# 4fader_Sub.net
KiCad netlist of a schematic drawn in Altium Designer
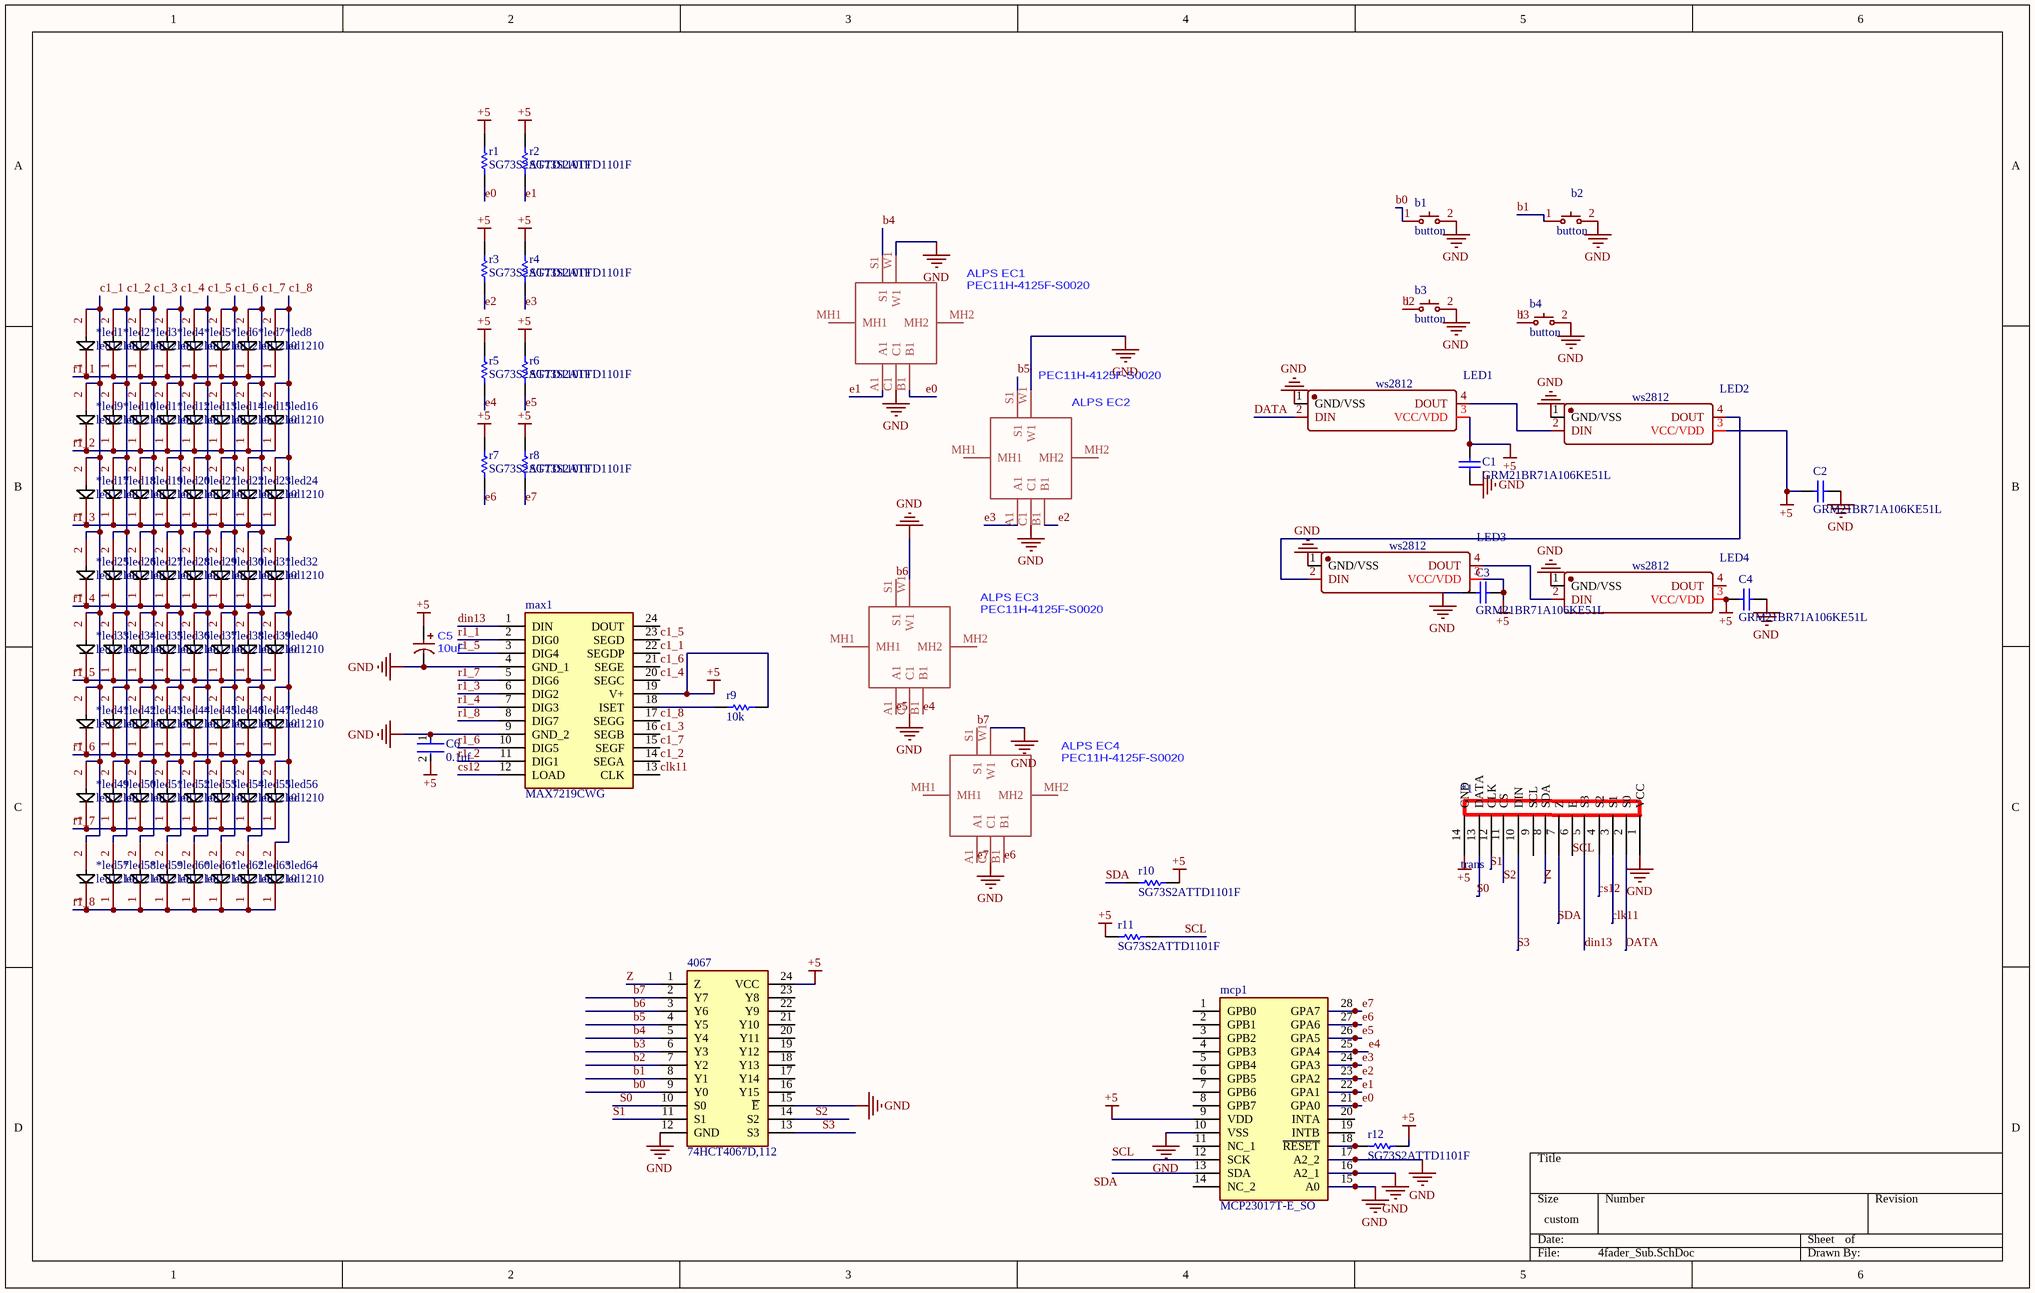
[diagram p0: 4fader_Sub.SchDoc]

(export (version "E")
  (design (tool "Eeschema 10.0.6"))
  (components
    (comp (ref "*1")
      (value "trans")
      (footprint "FPC-SMD_KH-FG1.0-H2.0-14PIN")
      (libsource (lib "sub_1") (part "trans"))
    )
    (comp (ref "*led1") (value "led1210") (footprint "1210贴片led") (libsource (lib "8") (part "led1210")))
    (comp (ref "*led2") (value "led1210") (footprint "1210贴片led") (libsource (lib "8") (part "led1210")))
    (comp (ref "*led3") (value "led1210") (footprint "1210贴片led") (libsource (lib "8") (part "led1210")))
    (comp (ref "*led4") (value "led1210") (footprint "1210贴片led") (libsource (lib "8") (part "led1210")))
    (comp (ref "*led5") (value "led1210") (footprint "1210贴片led") (libsource (lib "8") (part "led1210")))
    (comp (ref "*led6") (value "led1210") (footprint "1210贴片led") (libsource (lib "8") (part "led1210")))
    (comp (ref "*led7") (value "led1210") (footprint "1210贴片led") (libsource (lib "8") (part "led1210")))
    (comp (ref "*led8") (value "led1210") (footprint "1210贴片led") (libsource (lib "8") (part "led1210")))
    (comp (ref "*led9") (value "led1210") (footprint "1210贴片led") (libsource (lib "8") (part "led1210")))
    (comp (ref "*led10") (value "led1210") (footprint "1210贴片led") (libsource (lib "8") (part "led1210")))
    (comp (ref "*led11") (value "led1210") (footprint "1210贴片led") (libsource (lib "8") (part "led1210")))
    (comp (ref "*led12") (value "led1210") (footprint "1210贴片led") (libsource (lib "8") (part "led1210")))
    (comp (ref "*led13") (value "led1210") (footprint "1210贴片led") (libsource (lib "8") (part "led1210")))
    (comp (ref "*led14") (value "led1210") (footprint "1210贴片led") (libsource (lib "8") (part "led1210")))
    (comp (ref "*led15") (value "led1210") (footprint "1210贴片led") (libsource (lib "8") (part "led1210")))
    (comp (ref "*led16") (value "led1210") (footprint "1210贴片led") (libsource (lib "8") (part "led1210")))
    (comp (ref "*led17") (value "led1210") (footprint "1210贴片led") (libsource (lib "8") (part "led1210")))
    (comp (ref "*led18") (value "led1210") (footprint "1210贴片led") (libsource (lib "8") (part "led1210")))
    (comp (ref "*led19") (value "led1210") (footprint "1210贴片led") (libsource (lib "8") (part "led1210")))
    (comp (ref "*led20") (value "led1210") (footprint "1210贴片led") (libsource (lib "8") (part "led1210")))
    (comp (ref "*led21") (value "led1210") (footprint "1210贴片led") (libsource (lib "8") (part "led1210")))
    (comp (ref "*led22") (value "led1210") (footprint "1210贴片led") (libsource (lib "8") (part "led1210")))
    (comp (ref "*led23") (value "led1210") (footprint "1210贴片led") (libsource (lib "8") (part "led1210")))
    (comp (ref "*led24") (value "led1210") (footprint "1210贴片led") (libsource (lib "8") (part "led1210")))
    (comp (ref "*led25") (value "led1210") (footprint "1210贴片led") (libsource (lib "8") (part "led1210")))
    (comp (ref "*led26") (value "led1210") (footprint "1210贴片led") (libsource (lib "8") (part "led1210")))
    (comp (ref "*led27") (value "led1210") (footprint "1210贴片led") (libsource (lib "8") (part "led1210")))
    (comp (ref "*led28") (value "led1210") (footprint "1210贴片led") (libsource (lib "8") (part "led1210")))
    (comp (ref "*led29") (value "led1210") (footprint "1210贴片led") (libsource (lib "8") (part "led1210")))
    (comp (ref "*led30") (value "led1210") (footprint "1210贴片led") (libsource (lib "8") (part "led1210")))
    (comp (ref "*led31") (value "led1210") (footprint "1210贴片led") (libsource (lib "8") (part "led1210")))
    (comp (ref "*led32") (value "led1210") (footprint "1210贴片led") (libsource (lib "8") (part "led1210")))
    (comp (ref "*led33") (value "led1210") (footprint "1210贴片led") (libsource (lib "8") (part "led1210")))
    (comp (ref "*led34") (value "led1210") (footprint "1210贴片led") (libsource (lib "8") (part "led1210")))
    (comp (ref "*led35") (value "led1210") (footprint "1210贴片led") (libsource (lib "8") (part "led1210")))
    (comp (ref "*led36") (value "led1210") (footprint "1210贴片led") (libsource (lib "8") (part "led1210")))
    (comp (ref "*led37") (value "led1210") (footprint "1210贴片led") (libsource (lib "8") (part "led1210")))
    (comp (ref "*led38") (value "led1210") (footprint "1210贴片led") (libsource (lib "8") (part "led1210")))
    (comp (ref "*led39") (value "led1210") (footprint "1210贴片led") (libsource (lib "8") (part "led1210")))
    (comp (ref "*led40") (value "led1210") (footprint "1210贴片led") (libsource (lib "8") (part "led1210")))
    (comp (ref "*led41") (value "led1210") (footprint "1210贴片led") (libsource (lib "8") (part "led1210")))
    (comp (ref "*led42") (value "led1210") (footprint "1210贴片led") (libsource (lib "8") (part "led1210")))
    (comp (ref "*led43") (value "led1210") (footprint "1210贴片led") (libsource (lib "8") (part "led1210")))
    (comp (ref "*led44") (value "led1210") (footprint "1210贴片led") (libsource (lib "8") (part "led1210")))
    (comp (ref "*led45") (value "led1210") (footprint "1210贴片led") (libsource (lib "8") (part "led1210")))
    (comp (ref "*led46") (value "led1210") (footprint "1210贴片led") (libsource (lib "8") (part "led1210")))
    (comp (ref "*led47") (value "led1210") (footprint "1210贴片led") (libsource (lib "8") (part "led1210")))
    (comp (ref "*led48") (value "led1210") (footprint "1210贴片led") (libsource (lib "8") (part "led1210")))
    (comp (ref "*led49") (value "led1210") (footprint "1210贴片led") (libsource (lib "8") (part "led1210")))
    (comp (ref "*led50") (value "led1210") (footprint "1210贴片led") (libsource (lib "8") (part "led1210")))
    (comp (ref "*led51") (value "led1210") (footprint "1210贴片led") (libsource (lib "8") (part "led1210")))
    (comp (ref "*led52") (value "led1210") (footprint "1210贴片led") (libsource (lib "8") (part "led1210")))
    (comp (ref "*led53") (value "led1210") (footprint "1210贴片led") (libsource (lib "8") (part "led1210")))
    (comp (ref "*led54") (value "led1210") (footprint "1210贴片led") (libsource (lib "8") (part "led1210")))
    (comp (ref "*led55") (value "led1210") (footprint "1210贴片led") (libsource (lib "8") (part "led1210")))
    (comp (ref "*led56") (value "led1210") (footprint "1210贴片led") (libsource (lib "8") (part "led1210")))
    (comp (ref "*led57") (value "led1210") (footprint "1210贴片led") (libsource (lib "8") (part "led1210")))
    (comp (ref "*led58") (value "led1210") (footprint "1210贴片led") (libsource (lib "8") (part "led1210")))
    (comp (ref "*led59") (value "led1210") (footprint "1210贴片led") (libsource (lib "8") (part "led1210")))
    (comp (ref "*led60") (value "led1210") (footprint "1210贴片led") (libsource (lib "8") (part "led1210")))
    (comp (ref "*led61") (value "led1210") (footprint "1210贴片led") (libsource (lib "8") (part "led1210")))
    (comp (ref "*led62") (value "led1210") (footprint "1210贴片led") (libsource (lib "8") (part "led1210")))
    (comp (ref "*led63") (value "led1210") (footprint "1210贴片led") (libsource (lib "8") (part "led1210")))
    (comp (ref "*led64") (value "led1210") (footprint "1210贴片led") (libsource (lib "8") (part "led1210")))
    (comp (ref "4067")
      (value "74HCT4067D,112")
      (footprint "SamacSys:SOIC127P1032X265-24N")
      (description "Integrated Circuit")
      (fields (field (name "MOUSER PART NUMBER") "771-74HCT4067D"))
      (libsource (lib "*") (part "74HCT4067D,112"))
    )
    (comp (ref "ALPS EC1")
      (value "PEC11H-4125F-S0020")
      (footprint "ALPS EC11")
      (libsource (lib "8") (part "PEC11H-4125F-S0020"))
    )
    (comp (ref "ALPS EC2")
      (value "PEC11H-4125F-S0020")
      (footprint "ALPS EC11")
      (libsource (lib "8") (part "PEC11H-4125F-S0020"))
    )
    (comp (ref "ALPS EC3")
      (value "PEC11H-4125F-S0020")
      (footprint "ALPS EC11")
      (libsource (lib "8") (part "PEC11H-4125F-S0020"))
    )
    (comp (ref "ALPS EC4")
      (value "PEC11H-4125F-S0020")
      (footprint "ALPS EC11")
      (libsource (lib "8") (part "PEC11H-4125F-S0020"))
    )
    (comp (ref "b1") (value "button") (footprint "BUTTON") (libsource (lib "8") (part "button")))
    (comp (ref "b2") (value "button") (footprint "BUTTON") (libsource (lib "8") (part "button")))
    (comp (ref "b3") (value "button") (footprint "BUTTON") (libsource (lib "8") (part "button")))
    (comp (ref "b4") (value "button") (footprint "BUTTON") (libsource (lib "8") (part "button")))
    (comp (ref "C1")
      (value "GRM21BR71A106KE51L")
      (footprint "CAPC2013X140X45LL15T25")
      (fields (field (name "MANUFACTURER") "Murata"))
      (libsource (lib "sub_1") (part "CMP-2007-03395-1"))
    )
    (comp (ref "C2")
      (value "GRM21BR71A106KE51L")
      (footprint "CAPC2013X140X45LL15T25")
      (fields (field (name "MANUFACTURER") "Murata"))
      (libsource (lib "sub_1") (part "CMP-2007-03395-1"))
    )
    (comp (ref "C3")
      (value "GRM21BR71A106KE51L")
      (footprint "CAPC2013X140X45LL15T25")
      (fields (field (name "MANUFACTURER") "Murata"))
      (libsource (lib "sub_1") (part "CMP-2007-03395-1"))
    )
    (comp (ref "C4")
      (value "GRM21BR71A106KE51L")
      (footprint "CAPC2013X140X45LL15T25")
      (fields (field (name "MANUFACTURER") "Murata"))
      (libsource (lib "sub_1") (part "CMP-2007-03395-1"))
    )
    (comp (ref "C5")
      (value "10uF")
      (footprint "ELECTROLYTIC CAPACITOR SMD 4X5.4")
      (libsource (lib "sub_1") (part "4.3 X 4.3 ELECTROLYTIC  CAPACITOR SMD μF"))
    )
    (comp (ref "C6")
      (value "0.1uf")
      (footprint "FP-CC0805-0_85-IPC_A")
      (description "CAP CER 0.1UF 25V X7R 0805")
      (fields (field (name "MANUFACTURER PART NUMBER") "CC0805KRX7R8BB104") (field (name "TOLERANCE") "0.1"))
      (libsource (lib "sub_1") (part "CMP-1036-04410-2"))
    )
    (comp (ref "LED1") (value "ws2812") (footprint "ws2812") (libsource (lib "8") (part "ws2812")))
    (comp (ref "LED2") (value "ws2812") (footprint "ws2812") (libsource (lib "8") (part "ws2812")))
    (comp (ref "LED3") (value "ws2812") (footprint "ws2812") (libsource (lib "8") (part "ws2812")))
    (comp (ref "LED4") (value "ws2812") (footprint "ws2812") (libsource (lib "8") (part "ws2812")))
    (comp (ref "max1")
      (value "MAX7219CWG")
      (footprint "SamacSys:SOIC127P1032X265-24N")
      (description "Integrated Circuit")
      (fields (field (name "MOUSER PART NUMBER") "700-MAX7219CWG-NR"))
      (libsource (lib "*") (part "MAX7219CWG"))
    )
    (comp (ref "mcp1")
      (value "MCP23017T-E_SO")
      (footprint "SOIC127P1030X265-28N")
      (description "Integrated Circuit")
      (fields
        (field (name "MANUFACTURER_PART_NUMBER") "MCP23017T-E/SO")
        (field (name "MOUSER PART NUMBER") "579-MCP23017T-E/SO")
      )
      (libsource (lib "sub_1") (part "MCP23017T-E_SO"))
    )
    (comp (ref "r1")
      (value "SG73S2ATTD1101F")
      (footprint "RESC2013X60X30LL20T20")
      (fields (field (name "MANUFACTURER") "KOA Speer"))
      (libsource (lib "sub_1") (part "CMP-2001-02660-1"))
    )
    (comp (ref "r2")
      (value "SG73S2ATTD1101F")
      (footprint "RESC2013X60X30LL20T20")
      (fields (field (name "MANUFACTURER") "KOA Speer"))
      (libsource (lib "sub_1") (part "CMP-2001-02660-1"))
    )
    (comp (ref "r3")
      (value "SG73S2ATTD1101F")
      (footprint "RESC2013X60X30LL20T20")
      (fields (field (name "MANUFACTURER") "KOA Speer"))
      (libsource (lib "sub_1") (part "CMP-2001-02660-1"))
    )
    (comp (ref "r4")
      (value "SG73S2ATTD1101F")
      (footprint "RESC2013X60X30LL20T20")
      (fields (field (name "MANUFACTURER") "KOA Speer"))
      (libsource (lib "sub_1") (part "CMP-2001-02660-1"))
    )
    (comp (ref "r5")
      (value "SG73S2ATTD1101F")
      (footprint "RESC2013X60X30LL20T20")
      (fields (field (name "MANUFACTURER") "KOA Speer"))
      (libsource (lib "sub_1") (part "CMP-2001-02660-1"))
    )
    (comp (ref "r6")
      (value "SG73S2ATTD1101F")
      (footprint "RESC2013X60X30LL20T20")
      (fields (field (name "MANUFACTURER") "KOA Speer"))
      (libsource (lib "sub_1") (part "CMP-2001-02660-1"))
    )
    (comp (ref "r7")
      (value "SG73S2ATTD1101F")
      (footprint "RESC2013X60X30LL20T20")
      (fields (field (name "MANUFACTURER") "KOA Speer"))
      (libsource (lib "sub_1") (part "CMP-2001-02660-1"))
    )
    (comp (ref "r8")
      (value "SG73S2ATTD1101F")
      (footprint "RESC2013X60X30LL20T20")
      (fields (field (name "MANUFACTURER") "KOA Speer"))
      (libsource (lib "sub_1") (part "CMP-2001-02660-1"))
    )
    (comp (ref "r9")
      (value "10k")
      (footprint "RESC2013X60X30LL20T20")
      (fields (field (name "MANUFACTURER") "KOA Speer") (field (name "PART NUMBER") "SG73S2ATTD1101F"))
      (libsource (lib "sub_1") (part "CMP-2001-02660-1"))
    )
    (comp (ref "r10")
      (value "SG73S2ATTD1101F")
      (footprint "RESC2013X60X30LL20T20")
      (fields (field (name "MANUFACTURER") "KOA Speer"))
      (libsource (lib "sub_1") (part "CMP-2001-02660-1"))
    )
    (comp (ref "r11")
      (value "SG73S2ATTD1101F")
      (footprint "RESC2013X60X30LL20T20")
      (fields (field (name "MANUFACTURER") "KOA Speer"))
      (libsource (lib "sub_1") (part "CMP-2001-02660-1"))
    )
    (comp (ref "r12")
      (value "SG73S2ATTD1101F")
      (footprint "RESC2013X60X30LL20T20")
      (fields (field (name "MANUFACTURER") "KOA Speer"))
      (libsource (lib "sub_1") (part "CMP-2001-02660-1"))
    )
  )
  (nets
    (net (code "1") (name "+5") (class "Default")
      (node (ref "*1") (pin "14") (pinfunction "GND_14") (pintype "passive"))
      (node (ref "4067") (pin "24") (pinfunction "VCC_24") (pintype "passive"))
      (node (ref "C1") (pin "2") (pinfunction "2_2") (pintype "passive"))
      (node (ref "C2") (pin "1") (pinfunction "1_1") (pintype "passive"))
      (node (ref "C3") (pin "2") (pinfunction "2_2") (pintype "passive"))
      (node (ref "C4") (pin "1") (pinfunction "1_1") (pintype "passive"))
      (node (ref "C5") (pin "1") (pinfunction "1_1") (pintype "passive"))
      (node (ref "C6") (pin "2") (pinfunction "2_2") (pintype "passive"))
      (node (ref "LED1") (pin "3") (pinfunction "VCC/VDD_3") (pintype "passive"))
      (node (ref "LED2") (pin "3") (pinfunction "VCC/VDD_3") (pintype "passive"))
      (node (ref "LED3") (pin "3") (pinfunction "VCC/VDD_3") (pintype "passive"))
      (node (ref "LED4") (pin "3") (pinfunction "VCC/VDD_3") (pintype "passive"))
      (node (ref "max1") (pin "19") (pinfunction "V+_19") (pintype "passive"))
      (node (ref "mcp1") (pin "9") (pinfunction "VDD_9") (pintype "passive"))
      (node (ref "r1") (pin "2") (pinfunction "2_2") (pintype "passive"))
      (node (ref "r10") (pin "2") (pinfunction "2_2") (pintype "passive"))
      (node (ref "r11") (pin "2") (pinfunction "2_2") (pintype "passive"))
      (node (ref "r12") (pin "2") (pinfunction "2_2") (pintype "passive"))
      (node (ref "r2") (pin "2") (pinfunction "2_2") (pintype "passive"))
      (node (ref "r3") (pin "2") (pinfunction "2_2") (pintype "passive"))
      (node (ref "r4") (pin "2") (pinfunction "2_2") (pintype "passive"))
      (node (ref "r5") (pin "2") (pinfunction "2_2") (pintype "passive"))
      (node (ref "r6") (pin "2") (pinfunction "2_2") (pintype "passive"))
      (node (ref "r7") (pin "2") (pinfunction "2_2") (pintype "passive"))
      (node (ref "r8") (pin "2") (pinfunction "2_2") (pintype "passive"))
      (node (ref "r9") (pin "2") (pinfunction "2_2") (pintype "passive"))
    )
    (net (code "2") (name "/DATA") (class "Default")
      (node (ref "*1") (pin "2") (pinfunction "S0_2") (pintype "passive"))
      (node (ref "LED1") (pin "2") (pinfunction "DIN_2") (pintype "passive"))
    )
    (net (code "3") (name "/S0") (class "Default")
      (node (ref "*1") (pin "13") (pinfunction "DATA_13") (pintype "passive"))
      (node (ref "4067") (pin "10") (pinfunction "S0_10") (pintype "passive"))
    )
    (net (code "4") (name "/S1") (class "Default")
      (node (ref "*1") (pin "12") (pinfunction "CLK_12") (pintype "passive"))
      (node (ref "4067") (pin "11") (pinfunction "S1_11") (pintype "passive"))
    )
    (net (code "5") (name "/S2") (class "Default")
      (node (ref "*1") (pin "11") (pinfunction "CS_11") (pintype "passive"))
      (node (ref "4067") (pin "14") (pinfunction "S2_14") (pintype "passive"))
    )
    (net (code "6") (name "/S3") (class "Default")
      (node (ref "*1") (pin "10") (pinfunction "DIN_10") (pintype "passive"))
      (node (ref "4067") (pin "13") (pinfunction "S3_13") (pintype "passive"))
    )
    (net (code "7") (name "/SCL") (class "Default")
      (node (ref "*1") (pin "6") (pinfunction "E_6") (pintype "passive"))
      (node (ref "mcp1") (pin "12") (pinfunction "SCK_12") (pintype "passive"))
      (node (ref "r11") (pin "1") (pinfunction "1_1") (pintype "passive"))
    )
    (net (code "8") (name "/SDA") (class "Default")
      (node (ref "*1") (pin "7") (pinfunction "Z_7") (pintype "passive"))
      (node (ref "mcp1") (pin "13") (pinfunction "SDA_13") (pintype "passive"))
      (node (ref "r10") (pin "1") (pinfunction "1_1") (pintype "passive"))
    )
    (net (code "9") (name "/Z") (class "Default")
      (node (ref "*1") (pin "8") (pinfunction "SDA_8") (pintype "passive"))
      (node (ref "4067") (pin "1") (pinfunction "Z_1") (pintype "passive"))
    )
    (net (code "10") (name "/b0") (class "Default")
      (node (ref "4067") (pin "9") (pinfunction "Y0_9") (pintype "passive"))
      (node (ref "b1") (pin "1") (pinfunction "1_1") (pintype "passive"))
    )
    (net (code "11") (name "/b1") (class "Default")
      (node (ref "4067") (pin "8") (pinfunction "Y1_8") (pintype "passive"))
      (node (ref "b2") (pin "1") (pinfunction "1_1") (pintype "passive"))
    )
    (net (code "12") (name "/b2") (class "Default")
      (node (ref "4067") (pin "7") (pinfunction "Y2_7") (pintype "passive"))
      (node (ref "b3") (pin "1") (pinfunction "1_1") (pintype "passive"))
    )
    (net (code "13") (name "/b3") (class "Default")
      (node (ref "4067") (pin "6") (pinfunction "Y3_6") (pintype "passive"))
      (node (ref "b4") (pin "1") (pinfunction "1_1") (pintype "passive"))
    )
    (net (code "14") (name "/b4") (class "Default")
      (node (ref "4067") (pin "5") (pinfunction "Y4_5") (pintype "passive"))
      (node (ref "ALPS EC1") (pin "S1") (pinfunction "S1_S1") (pintype "passive"))
    )
    (net (code "15") (name "/b5") (class "Default")
      (node (ref "4067") (pin "4") (pinfunction "Y5_4") (pintype "passive"))
      (node (ref "ALPS EC2") (pin "S1") (pinfunction "S1_S1") (pintype "passive"))
    )
    (net (code "16") (name "/b6") (class "Default")
      (node (ref "4067") (pin "3") (pinfunction "Y6_3") (pintype "passive"))
      (node (ref "ALPS EC3") (pin "S1") (pinfunction "S1_S1") (pintype "passive"))
    )
    (net (code "17") (name "/b7") (class "Default")
      (node (ref "4067") (pin "2") (pinfunction "Y7_2") (pintype "passive"))
      (node (ref "ALPS EC4") (pin "S1") (pinfunction "S1_S1") (pintype "passive"))
    )
    (net (code "18") (name "/c1_1") (class "Default")
      (node (ref "*led1") (pin "2") (pinfunction "2_2") (pintype "passive"))
      (node (ref "*led17") (pin "2") (pinfunction "2_2") (pintype "passive"))
      (node (ref "*led25") (pin "2") (pinfunction "2_2") (pintype "passive"))
      (node (ref "*led33") (pin "2") (pinfunction "2_2") (pintype "passive"))
      (node (ref "*led41") (pin "2") (pinfunction "2_2") (pintype "passive"))
      (node (ref "*led49") (pin "2") (pinfunction "2_2") (pintype "passive"))
      (node (ref "*led57") (pin "2") (pinfunction "2_2") (pintype "passive"))
      (node (ref "*led9") (pin "2") (pinfunction "2_2") (pintype "passive"))
      (node (ref "max1") (pin "22") (pinfunction "SEGDP_22") (pintype "passive"))
    )
    (net (code "19") (name "/c1_2") (class "Default")
      (node (ref "*led10") (pin "2") (pinfunction "2_2") (pintype "passive"))
      (node (ref "*led18") (pin "2") (pinfunction "2_2") (pintype "passive"))
      (node (ref "*led2") (pin "2") (pinfunction "2_2") (pintype "passive"))
      (node (ref "*led26") (pin "2") (pinfunction "2_2") (pintype "passive"))
      (node (ref "*led34") (pin "2") (pinfunction "2_2") (pintype "passive"))
      (node (ref "*led42") (pin "2") (pinfunction "2_2") (pintype "passive"))
      (node (ref "*led50") (pin "2") (pinfunction "2_2") (pintype "passive"))
      (node (ref "*led58") (pin "2") (pinfunction "2_2") (pintype "passive"))
      (node (ref "max1") (pin "14") (pinfunction "SEGA_14") (pintype "passive"))
    )
    (net (code "20") (name "/c1_3") (class "Default")
      (node (ref "*led11") (pin "2") (pinfunction "2_2") (pintype "passive"))
      (node (ref "*led19") (pin "2") (pinfunction "2_2") (pintype "passive"))
      (node (ref "*led27") (pin "2") (pinfunction "2_2") (pintype "passive"))
      (node (ref "*led3") (pin "2") (pinfunction "2_2") (pintype "passive"))
      (node (ref "*led35") (pin "2") (pinfunction "2_2") (pintype "passive"))
      (node (ref "*led43") (pin "2") (pinfunction "2_2") (pintype "passive"))
      (node (ref "*led51") (pin "2") (pinfunction "2_2") (pintype "passive"))
      (node (ref "*led59") (pin "2") (pinfunction "2_2") (pintype "passive"))
      (node (ref "max1") (pin "16") (pinfunction "SEGB_16") (pintype "passive"))
    )
    (net (code "21") (name "/c1_4") (class "Default")
      (node (ref "*led12") (pin "2") (pinfunction "2_2") (pintype "passive"))
      (node (ref "*led20") (pin "2") (pinfunction "2_2") (pintype "passive"))
      (node (ref "*led28") (pin "2") (pinfunction "2_2") (pintype "passive"))
      (node (ref "*led36") (pin "2") (pinfunction "2_2") (pintype "passive"))
      (node (ref "*led4") (pin "2") (pinfunction "2_2") (pintype "passive"))
      (node (ref "*led44") (pin "2") (pinfunction "2_2") (pintype "passive"))
      (node (ref "*led52") (pin "2") (pinfunction "2_2") (pintype "passive"))
      (node (ref "*led60") (pin "2") (pinfunction "2_2") (pintype "passive"))
      (node (ref "max1") (pin "20") (pinfunction "SEGC_20") (pintype "passive"))
    )
    (net (code "22") (name "/c1_5") (class "Default")
      (node (ref "*led13") (pin "2") (pinfunction "2_2") (pintype "passive"))
      (node (ref "*led21") (pin "2") (pinfunction "2_2") (pintype "passive"))
      (node (ref "*led29") (pin "2") (pinfunction "2_2") (pintype "passive"))
      (node (ref "*led37") (pin "2") (pinfunction "2_2") (pintype "passive"))
      (node (ref "*led45") (pin "2") (pinfunction "2_2") (pintype "passive"))
      (node (ref "*led5") (pin "2") (pinfunction "2_2") (pintype "passive"))
      (node (ref "*led53") (pin "2") (pinfunction "2_2") (pintype "passive"))
      (node (ref "*led61") (pin "2") (pinfunction "2_2") (pintype "passive"))
      (node (ref "max1") (pin "23") (pinfunction "SEGD_23") (pintype "passive"))
    )
    (net (code "23") (name "/c1_6") (class "Default")
      (node (ref "*led14") (pin "2") (pinfunction "2_2") (pintype "passive"))
      (node (ref "*led22") (pin "2") (pinfunction "2_2") (pintype "passive"))
      (node (ref "*led30") (pin "2") (pinfunction "2_2") (pintype "passive"))
      (node (ref "*led38") (pin "2") (pinfunction "2_2") (pintype "passive"))
      (node (ref "*led46") (pin "2") (pinfunction "2_2") (pintype "passive"))
      (node (ref "*led54") (pin "2") (pinfunction "2_2") (pintype "passive"))
      (node (ref "*led6") (pin "2") (pinfunction "2_2") (pintype "passive"))
      (node (ref "*led62") (pin "2") (pinfunction "2_2") (pintype "passive"))
      (node (ref "max1") (pin "21") (pinfunction "SEGE_21") (pintype "passive"))
    )
    (net (code "24") (name "/c1_7") (class "Default")
      (node (ref "*led15") (pin "2") (pinfunction "2_2") (pintype "passive"))
      (node (ref "*led23") (pin "2") (pinfunction "2_2") (pintype "passive"))
      (node (ref "*led31") (pin "2") (pinfunction "2_2") (pintype "passive"))
      (node (ref "*led39") (pin "2") (pinfunction "2_2") (pintype "passive"))
      (node (ref "*led47") (pin "2") (pinfunction "2_2") (pintype "passive"))
      (node (ref "*led55") (pin "2") (pinfunction "2_2") (pintype "passive"))
      (node (ref "*led63") (pin "2") (pinfunction "2_2") (pintype "passive"))
      (node (ref "*led7") (pin "2") (pinfunction "2_2") (pintype "passive"))
      (node (ref "max1") (pin "15") (pinfunction "SEGF_15") (pintype "passive"))
    )
    (net (code "25") (name "/c1_8") (class "Default")
      (node (ref "*led16") (pin "2") (pinfunction "2_2") (pintype "passive"))
      (node (ref "*led24") (pin "2") (pinfunction "2_2") (pintype "passive"))
      (node (ref "*led32") (pin "2") (pinfunction "2_2") (pintype "passive"))
      (node (ref "*led40") (pin "2") (pinfunction "2_2") (pintype "passive"))
      (node (ref "*led48") (pin "2") (pinfunction "2_2") (pintype "passive"))
      (node (ref "*led56") (pin "2") (pinfunction "2_2") (pintype "passive"))
      (node (ref "*led64") (pin "2") (pinfunction "2_2") (pintype "passive"))
      (node (ref "*led8") (pin "2") (pinfunction "2_2") (pintype "passive"))
      (node (ref "max1") (pin "17") (pinfunction "SEGG_17") (pintype "passive"))
    )
    (net (code "26") (name "/clk11") (class "Default")
      (node (ref "*1") (pin "3") (pinfunction "S1_3") (pintype "passive"))
      (node (ref "max1") (pin "13") (pinfunction "CLK_13") (pintype "passive"))
    )
    (net (code "27") (name "/cs12") (class "Default")
      (node (ref "*1") (pin "4") (pinfunction "S2_4") (pintype "passive"))
      (node (ref "max1") (pin "12") (pinfunction "LOAD_12") (pintype "passive"))
    )
    (net (code "28") (name "/din13") (class "Default")
      (node (ref "*1") (pin "5") (pinfunction "S3_5") (pintype "passive"))
      (node (ref "max1") (pin "1") (pinfunction "DIN_1") (pintype "passive"))
    )
    (net (code "29") (name "/e0") (class "Default")
      (node (ref "ALPS EC1") (pin "B1") (pinfunction "B1_B1") (pintype "passive"))
      (node (ref "mcp1") (pin "21") (pinfunction "GPA0_21") (pintype "passive"))
      (node (ref "r1") (pin "1") (pinfunction "1_1") (pintype "passive"))
    )
    (net (code "30") (name "/e1") (class "Default")
      (node (ref "ALPS EC1") (pin "A1") (pinfunction "A1_A1") (pintype "passive"))
      (node (ref "mcp1") (pin "22") (pinfunction "GPA1_22") (pintype "passive"))
      (node (ref "r2") (pin "1") (pinfunction "1_1") (pintype "passive"))
    )
    (net (code "31") (name "/e2") (class "Default")
      (node (ref "ALPS EC2") (pin "B1") (pinfunction "B1_B1") (pintype "passive"))
      (node (ref "mcp1") (pin "23") (pinfunction "GPA2_23") (pintype "passive"))
      (node (ref "r3") (pin "1") (pinfunction "1_1") (pintype "passive"))
    )
    (net (code "32") (name "/e3") (class "Default")
      (node (ref "ALPS EC2") (pin "A1") (pinfunction "A1_A1") (pintype "passive"))
      (node (ref "mcp1") (pin "24") (pinfunction "GPA3_24") (pintype "passive"))
      (node (ref "r4") (pin "1") (pinfunction "1_1") (pintype "passive"))
    )
    (net (code "33") (name "/e4") (class "Default")
      (node (ref "ALPS EC3") (pin "B1") (pinfunction "B1_B1") (pintype "passive"))
      (node (ref "mcp1") (pin "25") (pinfunction "GPA4_25") (pintype "passive"))
      (node (ref "r5") (pin "1") (pinfunction "1_1") (pintype "passive"))
    )
    (net (code "34") (name "/e5") (class "Default")
      (node (ref "ALPS EC3") (pin "A1") (pinfunction "A1_A1") (pintype "passive"))
      (node (ref "mcp1") (pin "26") (pinfunction "GPA5_26") (pintype "passive"))
      (node (ref "r6") (pin "1") (pinfunction "1_1") (pintype "passive"))
    )
    (net (code "35") (name "/e6") (class "Default")
      (node (ref "ALPS EC4") (pin "B1") (pinfunction "B1_B1") (pintype "passive"))
      (node (ref "mcp1") (pin "27") (pinfunction "GPA6_27") (pintype "passive"))
      (node (ref "r7") (pin "1") (pinfunction "1_1") (pintype "passive"))
    )
    (net (code "36") (name "/e7") (class "Default")
      (node (ref "ALPS EC4") (pin "A1") (pinfunction "A1_A1") (pintype "passive"))
      (node (ref "mcp1") (pin "28") (pinfunction "GPA7_28") (pintype "passive"))
      (node (ref "r8") (pin "1") (pinfunction "1_1") (pintype "passive"))
    )
    (net (code "37") (name "/r1_1") (class "Default")
      (node (ref "*led1") (pin "1") (pinfunction "1_1") (pintype "passive"))
      (node (ref "*led2") (pin "1") (pinfunction "1_1") (pintype "passive"))
      (node (ref "*led3") (pin "1") (pinfunction "1_1") (pintype "passive"))
      (node (ref "*led4") (pin "1") (pinfunction "1_1") (pintype "passive"))
      (node (ref "*led5") (pin "1") (pinfunction "1_1") (pintype "passive"))
      (node (ref "*led6") (pin "1") (pinfunction "1_1") (pintype "passive"))
      (node (ref "*led7") (pin "1") (pinfunction "1_1") (pintype "passive"))
      (node (ref "*led8") (pin "1") (pinfunction "1_1") (pintype "passive"))
      (node (ref "max1") (pin "2") (pinfunction "DIG0_2") (pintype "passive"))
    )
    (net (code "38") (name "/r1_2") (class "Default")
      (node (ref "*led10") (pin "1") (pinfunction "1_1") (pintype "passive"))
      (node (ref "*led11") (pin "1") (pinfunction "1_1") (pintype "passive"))
      (node (ref "*led12") (pin "1") (pinfunction "1_1") (pintype "passive"))
      (node (ref "*led13") (pin "1") (pinfunction "1_1") (pintype "passive"))
      (node (ref "*led14") (pin "1") (pinfunction "1_1") (pintype "passive"))
      (node (ref "*led15") (pin "1") (pinfunction "1_1") (pintype "passive"))
      (node (ref "*led16") (pin "1") (pinfunction "1_1") (pintype "passive"))
      (node (ref "*led9") (pin "1") (pinfunction "1_1") (pintype "passive"))
      (node (ref "max1") (pin "11") (pinfunction "DIG1_11") (pintype "passive"))
    )
    (net (code "39") (name "/r1_3") (class "Default")
      (node (ref "*led17") (pin "1") (pinfunction "1_1") (pintype "passive"))
      (node (ref "*led18") (pin "1") (pinfunction "1_1") (pintype "passive"))
      (node (ref "*led19") (pin "1") (pinfunction "1_1") (pintype "passive"))
      (node (ref "*led20") (pin "1") (pinfunction "1_1") (pintype "passive"))
      (node (ref "*led21") (pin "1") (pinfunction "1_1") (pintype "passive"))
      (node (ref "*led22") (pin "1") (pinfunction "1_1") (pintype "passive"))
      (node (ref "*led23") (pin "1") (pinfunction "1_1") (pintype "passive"))
      (node (ref "*led24") (pin "1") (pinfunction "1_1") (pintype "passive"))
      (node (ref "max1") (pin "6") (pinfunction "DIG2_6") (pintype "passive"))
    )
    (net (code "40") (name "/r1_4") (class "Default")
      (node (ref "*led25") (pin "1") (pinfunction "1_1") (pintype "passive"))
      (node (ref "*led26") (pin "1") (pinfunction "1_1") (pintype "passive"))
      (node (ref "*led27") (pin "1") (pinfunction "1_1") (pintype "passive"))
      (node (ref "*led28") (pin "1") (pinfunction "1_1") (pintype "passive"))
      (node (ref "*led29") (pin "1") (pinfunction "1_1") (pintype "passive"))
      (node (ref "*led30") (pin "1") (pinfunction "1_1") (pintype "passive"))
      (node (ref "*led31") (pin "1") (pinfunction "1_1") (pintype "passive"))
      (node (ref "*led32") (pin "1") (pinfunction "1_1") (pintype "passive"))
      (node (ref "max1") (pin "7") (pinfunction "DIG3_7") (pintype "passive"))
    )
    (net (code "41") (name "/r1_5") (class "Default")
      (node (ref "*led33") (pin "1") (pinfunction "1_1") (pintype "passive"))
      (node (ref "*led34") (pin "1") (pinfunction "1_1") (pintype "passive"))
      (node (ref "*led35") (pin "1") (pinfunction "1_1") (pintype "passive"))
      (node (ref "*led36") (pin "1") (pinfunction "1_1") (pintype "passive"))
      (node (ref "*led37") (pin "1") (pinfunction "1_1") (pintype "passive"))
      (node (ref "*led38") (pin "1") (pinfunction "1_1") (pintype "passive"))
      (node (ref "*led39") (pin "1") (pinfunction "1_1") (pintype "passive"))
      (node (ref "*led40") (pin "1") (pinfunction "1_1") (pintype "passive"))
      (node (ref "max1") (pin "3") (pinfunction "DIG4_3") (pintype "passive"))
    )
    (net (code "42") (name "/r1_6") (class "Default")
      (node (ref "*led41") (pin "1") (pinfunction "1_1") (pintype "passive"))
      (node (ref "*led42") (pin "1") (pinfunction "1_1") (pintype "passive"))
      (node (ref "*led43") (pin "1") (pinfunction "1_1") (pintype "passive"))
      (node (ref "*led44") (pin "1") (pinfunction "1_1") (pintype "passive"))
      (node (ref "*led45") (pin "1") (pinfunction "1_1") (pintype "passive"))
      (node (ref "*led46") (pin "1") (pinfunction "1_1") (pintype "passive"))
      (node (ref "*led47") (pin "1") (pinfunction "1_1") (pintype "passive"))
      (node (ref "*led48") (pin "1") (pinfunction "1_1") (pintype "passive"))
      (node (ref "max1") (pin "10") (pinfunction "DIG5_10") (pintype "passive"))
    )
    (net (code "43") (name "/r1_7") (class "Default")
      (node (ref "*led49") (pin "1") (pinfunction "1_1") (pintype "passive"))
      (node (ref "*led50") (pin "1") (pinfunction "1_1") (pintype "passive"))
      (node (ref "*led51") (pin "1") (pinfunction "1_1") (pintype "passive"))
      (node (ref "*led52") (pin "1") (pinfunction "1_1") (pintype "passive"))
      (node (ref "*led53") (pin "1") (pinfunction "1_1") (pintype "passive"))
      (node (ref "*led54") (pin "1") (pinfunction "1_1") (pintype "passive"))
      (node (ref "*led55") (pin "1") (pinfunction "1_1") (pintype "passive"))
      (node (ref "*led56") (pin "1") (pinfunction "1_1") (pintype "passive"))
      (node (ref "max1") (pin "5") (pinfunction "DIG6_5") (pintype "passive"))
    )
    (net (code "44") (name "/r1_8") (class "Default")
      (node (ref "*led57") (pin "1") (pinfunction "1_1") (pintype "passive"))
      (node (ref "*led58") (pin "1") (pinfunction "1_1") (pintype "passive"))
      (node (ref "*led59") (pin "1") (pinfunction "1_1") (pintype "passive"))
      (node (ref "*led60") (pin "1") (pinfunction "1_1") (pintype "passive"))
      (node (ref "*led61") (pin "1") (pinfunction "1_1") (pintype "passive"))
      (node (ref "*led62") (pin "1") (pinfunction "1_1") (pintype "passive"))
      (node (ref "*led63") (pin "1") (pinfunction "1_1") (pintype "passive"))
      (node (ref "*led64") (pin "1") (pinfunction "1_1") (pintype "passive"))
      (node (ref "max1") (pin "8") (pinfunction "DIG7_8") (pintype "passive"))
    )
    (net (code "45") (name "GND") (class "Default")
      (node (ref "*1") (pin "1") (pinfunction "VCC_1") (pintype "passive"))
      (node (ref "4067") (pin "12") (pinfunction "GND_12") (pintype "passive"))
      (node (ref "4067") (pin "15") (pinfunction "~{E}_15") (pintype "passive"))
      (node (ref "ALPS EC1") (pin "C1") (pinfunction "C1_C1") (pintype "passive"))
      (node (ref "ALPS EC1") (pin "W1") (pinfunction "W1_W1") (pintype "passive"))
      (node (ref "ALPS EC2") (pin "C1") (pinfunction "C1_C1") (pintype "passive"))
      (node (ref "ALPS EC2") (pin "W1") (pinfunction "W1_W1") (pintype "passive"))
      (node (ref "ALPS EC3") (pin "C1") (pinfunction "C1_C1") (pintype "passive"))
      (node (ref "ALPS EC3") (pin "W1") (pinfunction "W1_W1") (pintype "passive"))
      (node (ref "ALPS EC4") (pin "C1") (pinfunction "C1_C1") (pintype "passive"))
      (node (ref "ALPS EC4") (pin "W1") (pinfunction "W1_W1") (pintype "passive"))
      (node (ref "C1") (pin "1") (pinfunction "1_1") (pintype "passive"))
      (node (ref "C2") (pin "2") (pinfunction "2_2") (pintype "passive"))
      (node (ref "C3") (pin "1") (pinfunction "1_1") (pintype "passive"))
      (node (ref "C4") (pin "2") (pinfunction "2_2") (pintype "passive"))
      (node (ref "C5") (pin "2") (pinfunction "2_2") (pintype "passive"))
      (node (ref "C6") (pin "1") (pinfunction "1_1") (pintype "passive"))
      (node (ref "LED1") (pin "1") (pinfunction "GND/VSS_1") (pintype "passive"))
      (node (ref "LED2") (pin "1") (pinfunction "GND/VSS_1") (pintype "passive"))
      (node (ref "LED3") (pin "1") (pinfunction "GND/VSS_1") (pintype "passive"))
      (node (ref "LED4") (pin "1") (pinfunction "GND/VSS_1") (pintype "passive"))
      (node (ref "b1") (pin "2") (pinfunction "2_2") (pintype "passive"))
      (node (ref "b2") (pin "2") (pinfunction "2_2") (pintype "passive"))
      (node (ref "b3") (pin "2") (pinfunction "2_2") (pintype "passive"))
      (node (ref "b4") (pin "2") (pinfunction "2_2") (pintype "passive"))
      (node (ref "max1") (pin "4") (pinfunction "GND_1_4") (pintype "passive"))
      (node (ref "max1") (pin "9") (pinfunction "GND_2_9") (pintype "passive"))
      (node (ref "mcp1") (pin "10") (pinfunction "VSS_10") (pintype "passive"))
      (node (ref "mcp1") (pin "15") (pinfunction "A0_15") (pintype "passive"))
      (node (ref "mcp1") (pin "16") (pinfunction "A2_1_16") (pintype "passive"))
      (node (ref "mcp1") (pin "17") (pinfunction "A2_2_17") (pintype "passive"))
    )
    (net (code "46") (name "Net-(LED1-DOUT)") (class "Default")
      (node (ref "LED1") (pin "4") (pinfunction "DOUT_4") (pintype "passive"))
      (node (ref "LED2") (pin "2") (pinfunction "DIN_2") (pintype "passive"))
    )
    (net (code "47") (name "Net-(LED2-DOUT)") (class "Default")
      (node (ref "LED2") (pin "4") (pinfunction "DOUT_4") (pintype "passive"))
      (node (ref "LED3") (pin "2") (pinfunction "DIN_2") (pintype "passive"))
    )
    (net (code "48") (name "Net-(LED3-DOUT)") (class "Default")
      (node (ref "LED3") (pin "4") (pinfunction "DOUT_4") (pintype "passive"))
      (node (ref "LED4") (pin "2") (pinfunction "DIN_2") (pintype "passive"))
    )
    (net (code "49") (name "Net-(max1-ISET)") (class "Default")
      (node (ref "max1") (pin "18") (pinfunction "ISET_18") (pintype "passive"))
      (node (ref "r9") (pin "1") (pinfunction "1_1") (pintype "passive"))
    )
    (net (code "50") (name "Net-(mcp1-~{RESET})") (class "Default")
      (node (ref "mcp1") (pin "18") (pinfunction "~{RESET}_18") (pintype "passive"))
      (node (ref "r12") (pin "1") (pinfunction "1_1") (pintype "passive"))
    )
    (net (code "51") (name "unconnected-(*1-SCL-Pad9)") (class "Default")
      (node (ref "*1") (pin "9") (pinfunction "SCL_9") (pintype "passive"))
    )
    (net (code "52") (name "unconnected-(4067-Y8-Pad23)") (class "Default")
      (node (ref "4067") (pin "23") (pinfunction "Y8_23") (pintype "passive"))
    )
    (net (code "53") (name "unconnected-(4067-Y9-Pad22)") (class "Default")
      (node (ref "4067") (pin "22") (pinfunction "Y9_22") (pintype "passive"))
    )
    (net (code "54") (name "unconnected-(4067-Y10-Pad21)") (class "Default")
      (node (ref "4067") (pin "21") (pinfunction "Y10_21") (pintype "passive"))
    )
    (net (code "55") (name "unconnected-(4067-Y11-Pad20)") (class "Default")
      (node (ref "4067") (pin "20") (pinfunction "Y11_20") (pintype "passive"))
    )
    (net (code "56") (name "unconnected-(4067-Y12-Pad19)") (class "Default")
      (node (ref "4067") (pin "19") (pinfunction "Y12_19") (pintype "passive"))
    )
    (net (code "57") (name "unconnected-(4067-Y13-Pad18)") (class "Default")
      (node (ref "4067") (pin "18") (pinfunction "Y13_18") (pintype "passive"))
    )
    (net (code "58") (name "unconnected-(4067-Y14-Pad17)") (class "Default")
      (node (ref "4067") (pin "17") (pinfunction "Y14_17") (pintype "passive"))
    )
    (net (code "59") (name "unconnected-(4067-Y15-Pad16)") (class "Default")
      (node (ref "4067") (pin "16") (pinfunction "Y15_16") (pintype "passive"))
    )
    (net (code "60") (name "unconnected-(ALPS EC1-PadMH1)") (class "Default")
      (node (ref "ALPS EC1") (pin "MH1") (pinfunction "MH1_MH1") (pintype "passive"))
    )
    (net (code "61") (name "unconnected-(ALPS EC1-PadMH2)") (class "Default")
      (node (ref "ALPS EC1") (pin "MH2") (pinfunction "MH2_MH2") (pintype "passive"))
    )
    (net (code "62") (name "unconnected-(ALPS EC2-PadMH1)") (class "Default")
      (node (ref "ALPS EC2") (pin "MH1") (pinfunction "MH1_MH1") (pintype "passive"))
    )
    (net (code "63") (name "unconnected-(ALPS EC2-PadMH2)") (class "Default")
      (node (ref "ALPS EC2") (pin "MH2") (pinfunction "MH2_MH2") (pintype "passive"))
    )
    (net (code "64") (name "unconnected-(ALPS EC3-PadMH1)") (class "Default")
      (node (ref "ALPS EC3") (pin "MH1") (pinfunction "MH1_MH1") (pintype "passive"))
    )
    (net (code "65") (name "unconnected-(ALPS EC3-PadMH2)") (class "Default")
      (node (ref "ALPS EC3") (pin "MH2") (pinfunction "MH2_MH2") (pintype "passive"))
    )
    (net (code "66") (name "unconnected-(ALPS EC4-PadMH1)") (class "Default")
      (node (ref "ALPS EC4") (pin "MH1") (pinfunction "MH1_MH1") (pintype "passive"))
    )
    (net (code "67") (name "unconnected-(ALPS EC4-PadMH2)") (class "Default")
      (node (ref "ALPS EC4") (pin "MH2") (pinfunction "MH2_MH2") (pintype "passive"))
    )
    (net (code "68") (name "unconnected-(LED4-DOUT-Pad4)") (class "Default")
      (node (ref "LED4") (pin "4") (pinfunction "DOUT_4") (pintype "passive"))
    )
    (net (code "69") (name "unconnected-(max1-DOUT-Pad24)") (class "Default")
      (node (ref "max1") (pin "24") (pinfunction "DOUT_24") (pintype "passive"))
    )
    (net (code "70") (name "unconnected-(mcp1-GPB0-Pad1)") (class "Default")
      (node (ref "mcp1") (pin "1") (pinfunction "GPB0_1") (pintype "passive"))
    )
    (net (code "71") (name "unconnected-(mcp1-GPB1-Pad2)") (class "Default")
      (node (ref "mcp1") (pin "2") (pinfunction "GPB1_2") (pintype "passive"))
    )
    (net (code "72") (name "unconnected-(mcp1-GPB2-Pad3)") (class "Default")
      (node (ref "mcp1") (pin "3") (pinfunction "GPB2_3") (pintype "passive"))
    )
    (net (code "73") (name "unconnected-(mcp1-GPB3-Pad4)") (class "Default")
      (node (ref "mcp1") (pin "4") (pinfunction "GPB3_4") (pintype "passive"))
    )
    (net (code "74") (name "unconnected-(mcp1-GPB4-Pad5)") (class "Default")
      (node (ref "mcp1") (pin "5") (pinfunction "GPB4_5") (pintype "passive"))
    )
    (net (code "75") (name "unconnected-(mcp1-GPB5-Pad6)") (class "Default")
      (node (ref "mcp1") (pin "6") (pinfunction "GPB5_6") (pintype "passive"))
    )
    (net (code "76") (name "unconnected-(mcp1-GPB6-Pad7)") (class "Default")
      (node (ref "mcp1") (pin "7") (pinfunction "GPB6_7") (pintype "passive"))
    )
    (net (code "77") (name "unconnected-(mcp1-GPB7-Pad8)") (class "Default")
      (node (ref "mcp1") (pin "8") (pinfunction "GPB7_8") (pintype "passive"))
    )
    (net (code "78") (name "unconnected-(mcp1-INTA-Pad20)") (class "Default")
      (node (ref "mcp1") (pin "20") (pinfunction "INTA_20") (pintype "passive"))
    )
    (net (code "79") (name "unconnected-(mcp1-INTB-Pad19)") (class "Default")
      (node (ref "mcp1") (pin "19") (pinfunction "INTB_19") (pintype "passive"))
    )
    (net (code "80") (name "unconnected-(mcp1-NC_1-Pad11)") (class "Default")
      (node (ref "mcp1") (pin "11") (pinfunction "NC_1_11") (pintype "passive"))
    )
    (net (code "81") (name "unconnected-(mcp1-NC_2-Pad14)") (class "Default")
      (node (ref "mcp1") (pin "14") (pinfunction "NC_2_14") (pintype "passive"))
    )
  )
)
